# WebServer3_shield_wSD_FTDI.net
KiCad netlist of a schematic drawn in EAGLE
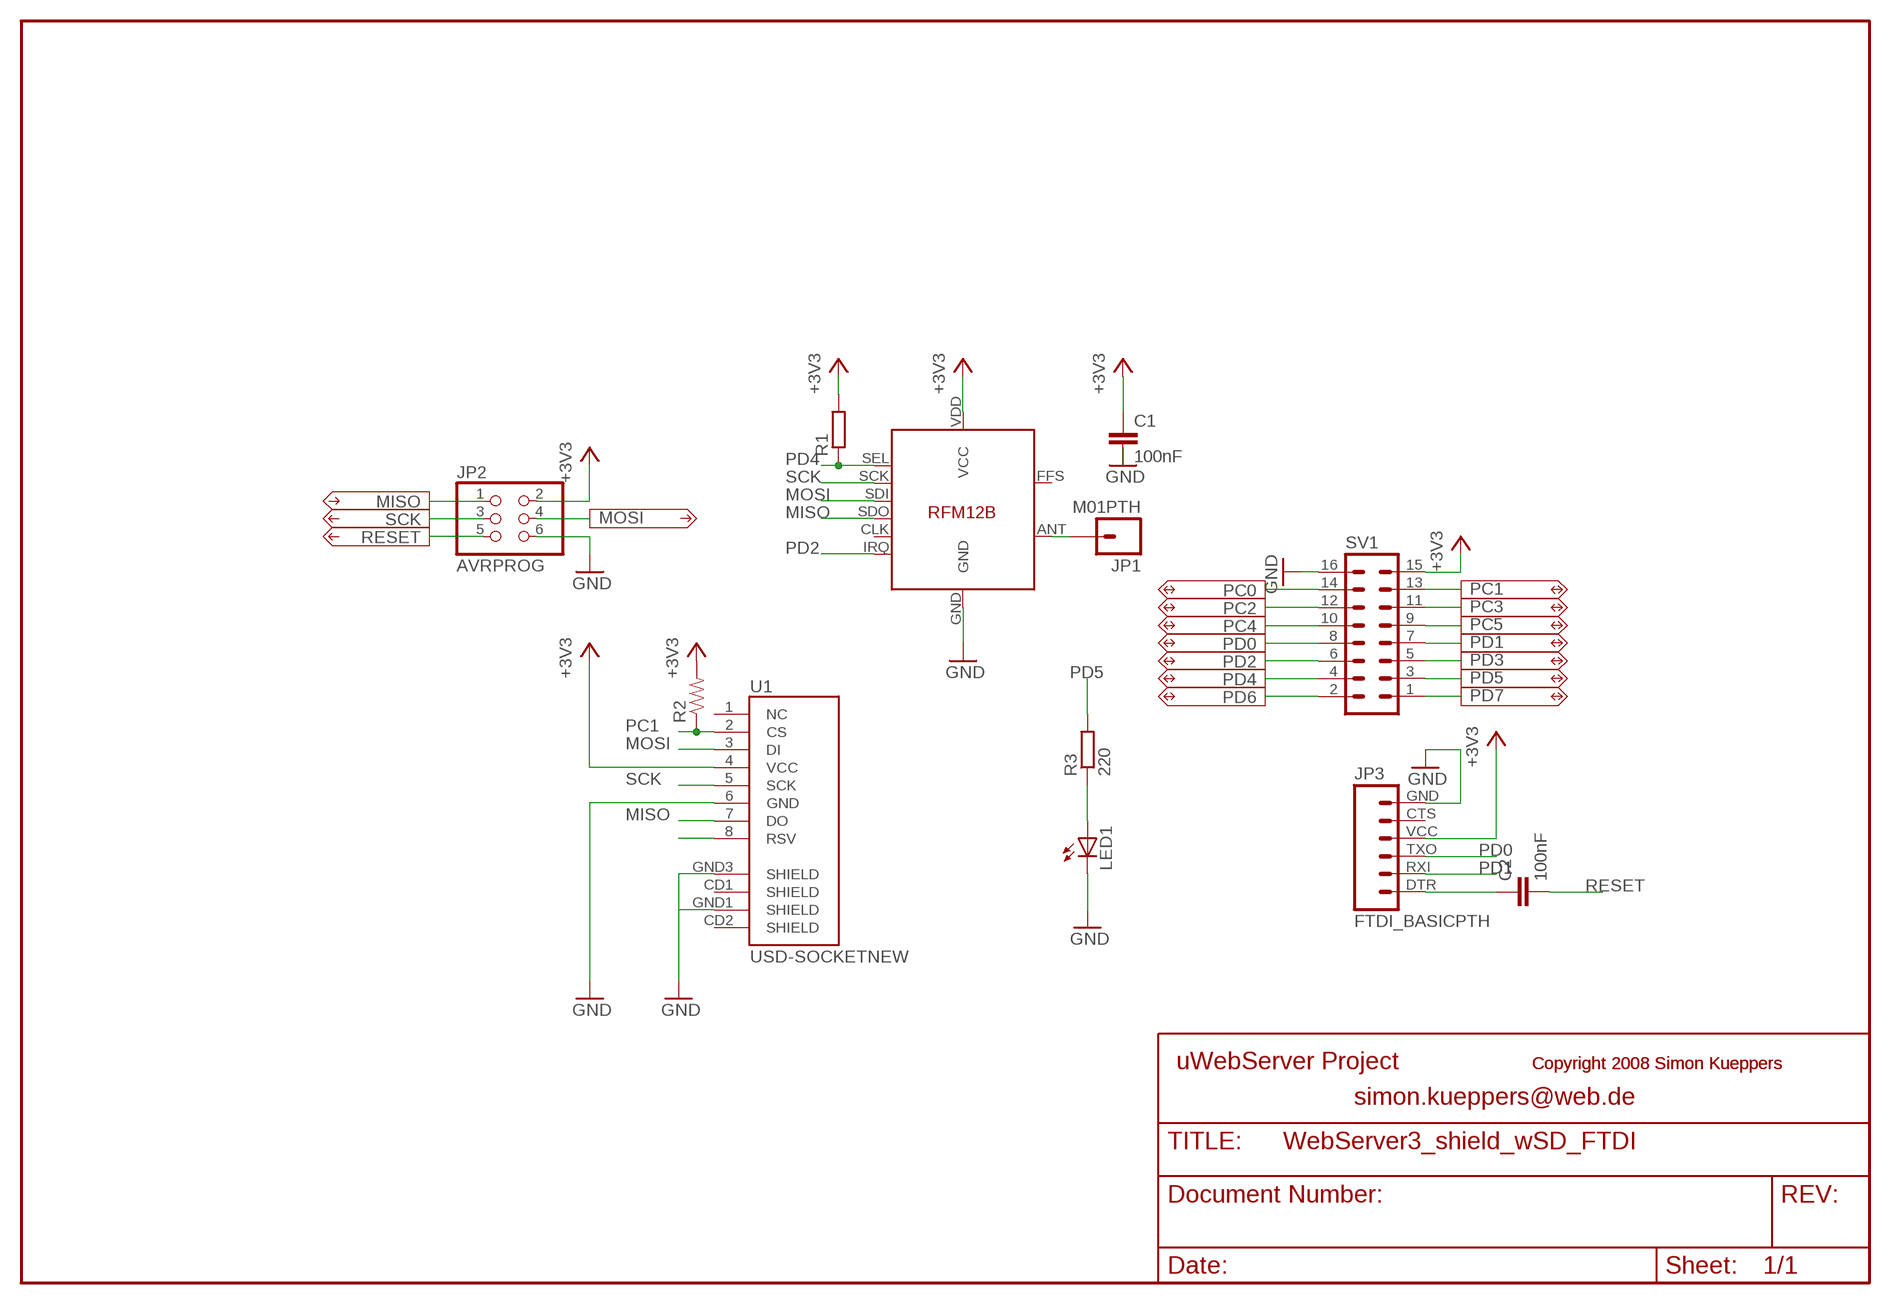
[diagram p0: schematic, sheet 1]

(export (version "E")
  (design (tool "Eeschema 10.0.6"))
  (components
    (comp (ref "C1")
      (value "100nF")
      (footprint "eagle-import:C0805")
      (libsource (lib "eagle-import") (part "C-EUC0805"))
    )
    (comp (ref "C2")
      (value "100nF")
      (footprint "eagle-import:C0805")
      (libsource (lib "eagle-import") (part "C-EUC0805"))
    )
    (comp (ref "JP1")
      (value "M01PTH")
      (footprint "eagle-import:1X01")
      (libsource (lib "eagle-import") (part "M01PTH"))
    )
    (comp (ref "JP2")
      (value "AVRPROG")
      (footprint "eagle-import:2X03")
      (libsource (lib "eagle-import") (part "PINHD-2X3_2.54"))
    )
    (comp (ref "JP3")
      (value "FTDI_BASICPTH")
      (footprint "eagle-import:FTDI_BASIC")
      (libsource (lib "eagle-import") (part "FTDI_BASICPTH"))
    )
    (comp (ref "LED1")
      (value "LED0603")
      (footprint "eagle-import:LED-0603")
      (libsource (lib "eagle-import") (part "LED0603"))
    )
    (comp (ref "R1")
      (value "R-EU_R0805")
      (footprint "eagle-import:R0805")
      (libsource (lib "eagle-import") (part "R-EU_R0805"))
    )
    (comp (ref "R2")
      (value "RESISTOR0805-RES")
      (footprint "eagle-import:0805")
      (libsource (lib "eagle-import") (part "RESISTOR0805-RES"))
    )
    (comp (ref "R3")
      (value "220")
      (footprint "eagle-import:R0805")
      (libsource (lib "eagle-import") (part "R-EU_R0805"))
    )
    (comp (ref "RFM12B")
      (value "RFM12B")
      (footprint "eagle-import:RFM12B")
      (libsource (lib "eagle-import") (part "RFM12B"))
    )
    (comp (ref "SV1")
      (value "MA08-2")
      (footprint "eagle-import:MA08-2")
      (libsource (lib "eagle-import") (part "MA08-2"))
    )
    (comp (ref "U1")
      (value "USD-SOCKETNEW")
      (footprint "eagle-import:MICRO-SD-SOCKET-PP")
      (libsource (lib "eagle-import") (part "USD-SOCKETNEW"))
    )
  )
  (nets
    (net (code "1") (name "+3V3") (class "Default")
      (node (ref "C1") (pin "1") (pinfunction "1_1") (pintype "passive"))
      (node (ref "JP2") (pin "2") (pinfunction "2_2") (pintype "passive"))
      (node (ref "JP3") (pin "VCC") (pinfunction "4_VCC") (pintype "passive"))
      (node (ref "R1") (pin "2") (pinfunction "2_2") (pintype "passive"))
      (node (ref "R2") (pin "2") (pinfunction "2_2") (pintype "passive"))
      (node (ref "RFM12B") (pin "VDD") (pinfunction "VCC_VDD") (pintype "power_in"))
      (node (ref "SV1") (pin "15") (pinfunction "15_15") (pintype "passive"))
      (node (ref "U1") (pin "4") (pinfunction "VCC_4") (pintype "bidirectional"))
    )
    (net (code "2") (name "/MISO") (class "Default")
      (node (ref "JP2") (pin "1") (pinfunction "1_1") (pintype "passive"))
      (node (ref "RFM12B") (pin "SDO") (pinfunction "SDO_SDO") (pintype "output"))
      (node (ref "U1") (pin "7") (pinfunction "DO_7") (pintype "bidirectional"))
    )
    (net (code "3") (name "/MOSI") (class "Default")
      (node (ref "JP2") (pin "4") (pinfunction "4_4") (pintype "passive"))
      (node (ref "RFM12B") (pin "SDI") (pinfunction "SDI_SDI") (pintype "input"))
      (node (ref "U1") (pin "3") (pinfunction "DI_3") (pintype "bidirectional"))
    )
    (net (code "4") (name "/PC1") (class "Default")
      (node (ref "R2") (pin "1") (pinfunction "1_1") (pintype "passive"))
      (node (ref "SV1") (pin "13") (pinfunction "13_13") (pintype "passive"))
      (node (ref "U1") (pin "2") (pinfunction "CS_2") (pintype "bidirectional"))
    )
    (net (code "5") (name "/PD0") (class "Default")
      (node (ref "JP3") (pin "TXO") (pinfunction "3_TXO") (pintype "passive"))
      (node (ref "SV1") (pin "8") (pinfunction "8_8") (pintype "passive"))
    )
    (net (code "6") (name "/PD1") (class "Default")
      (node (ref "JP3") (pin "RXI") (pinfunction "2_RXI") (pintype "passive"))
      (node (ref "SV1") (pin "7") (pinfunction "7_7") (pintype "passive"))
    )
    (net (code "7") (name "/PD2") (class "Default")
      (node (ref "RFM12B") (pin "IRQ") (pinfunction "IRQ_IRQ") (pintype "open_collector"))
      (node (ref "SV1") (pin "6") (pinfunction "6_6") (pintype "passive"))
    )
    (net (code "8") (name "/PD4") (class "Default")
      (node (ref "R1") (pin "1") (pinfunction "1_1") (pintype "passive"))
      (node (ref "RFM12B") (pin "SEL") (pinfunction "SEL_SEL") (pintype "input"))
      (node (ref "SV1") (pin "4") (pinfunction "4_4") (pintype "passive"))
    )
    (net (code "9") (name "/PD5") (class "Default")
      (node (ref "R3") (pin "2") (pinfunction "2_2") (pintype "passive"))
      (node (ref "SV1") (pin "3") (pinfunction "3_3") (pintype "passive"))
    )
    (net (code "10") (name "/RESET") (class "Default")
      (node (ref "C2") (pin "2") (pinfunction "2_2") (pintype "passive"))
      (node (ref "JP2") (pin "5") (pinfunction "5_5") (pintype "passive"))
    )
    (net (code "11") (name "/SCK") (class "Default")
      (node (ref "JP2") (pin "3") (pinfunction "3_3") (pintype "passive"))
      (node (ref "RFM12B") (pin "SCK") (pinfunction "SCK_SCK") (pintype "input"))
      (node (ref "U1") (pin "5") (pinfunction "SCK_5") (pintype "bidirectional"))
    )
    (net (code "12") (name "GND") (class "Default")
      (node (ref "C1") (pin "2") (pinfunction "2_2") (pintype "passive"))
      (node (ref "JP2") (pin "6") (pinfunction "6_6") (pintype "passive"))
      (node (ref "JP3") (pin "GND") (pinfunction "6_GND") (pintype "passive"))
      (node (ref "LED1") (pin "C") (pinfunction "C_C") (pintype "passive"))
      (node (ref "RFM12B") (pin "GND") (pinfunction "GND_GND") (pintype "power_in"))
      (node (ref "SV1") (pin "16") (pinfunction "16_16") (pintype "passive"))
      (node (ref "U1") (pin "6") (pinfunction "GND_6") (pintype "bidirectional"))
      (node (ref "U1") (pin "GND3") (pinfunction "SHIELD_GND3") (pintype "bidirectional"))
    )
    (net (code "13") (name "Net-(JP1-Pad1)") (class "Default")
      (node (ref "JP1") (pin "1") (pinfunction "1_1") (pintype "passive"))
      (node (ref "RFM12B") (pin "ANT") (pinfunction "ANT_ANT") (pintype "passive"))
    )
    (net (code "14") (name "Net-(JP3-1)") (class "Default")
      (node (ref "C2") (pin "1") (pinfunction "1_1") (pintype "passive"))
      (node (ref "JP3") (pin "DTR") (pinfunction "1_DTR") (pintype "passive"))
    )
    (net (code "15") (name "Net-(LED1-PadA)") (class "Default")
      (node (ref "LED1") (pin "A") (pinfunction "A_A") (pintype "passive"))
      (node (ref "R3") (pin "1") (pinfunction "1_1") (pintype "passive"))
    )
    (net (code "16") (name "unconnected-(JP3-5-PadCTS)") (class "Default")
      (node (ref "JP3") (pin "CTS") (pinfunction "5_CTS") (pintype "passive"))
    )
    (net (code "17") (name "unconnected-(RFM12B-PadCLK)") (class "Default")
      (node (ref "RFM12B") (pin "CLK") (pinfunction "CLK_CLK") (pintype "output"))
    )
    (net (code "18") (name "unconnected-(RFM12B-PadFFS)") (class "Default")
      (node (ref "RFM12B") (pin "FFS") (pinfunction "FFS_FFS") (pintype "bidirectional"))
    )
    (net (code "19") (name "unconnected-(SV1-Pad1)") (class "Default")
      (node (ref "SV1") (pin "1") (pinfunction "1_1") (pintype "passive"))
    )
    (net (code "20") (name "unconnected-(SV1-Pad2)") (class "Default")
      (node (ref "SV1") (pin "2") (pinfunction "2_2") (pintype "passive"))
    )
    (net (code "21") (name "unconnected-(SV1-Pad5)") (class "Default")
      (node (ref "SV1") (pin "5") (pinfunction "5_5") (pintype "passive"))
    )
    (net (code "22") (name "unconnected-(SV1-Pad9)") (class "Default")
      (node (ref "SV1") (pin "9") (pinfunction "9_9") (pintype "passive"))
    )
    (net (code "23") (name "unconnected-(SV1-Pad10)") (class "Default")
      (node (ref "SV1") (pin "10") (pinfunction "10_10") (pintype "passive"))
    )
    (net (code "24") (name "unconnected-(SV1-Pad11)") (class "Default")
      (node (ref "SV1") (pin "11") (pinfunction "11_11") (pintype "passive"))
    )
    (net (code "25") (name "unconnected-(SV1-Pad12)") (class "Default")
      (node (ref "SV1") (pin "12") (pinfunction "12_12") (pintype "passive"))
    )
    (net (code "26") (name "unconnected-(SV1-Pad14)") (class "Default")
      (node (ref "SV1") (pin "14") (pinfunction "14_14") (pintype "passive"))
    )
    (net (code "27") (name "unconnected-(U1-NC-Pad1)") (class "Default")
      (node (ref "U1") (pin "1") (pinfunction "NC_1") (pintype "bidirectional"))
    )
    (net (code "28") (name "unconnected-(U1-RSV-Pad8)") (class "Default")
      (node (ref "U1") (pin "8") (pinfunction "RSV_8") (pintype "bidirectional"))
    )
    (net (code "29") (name "unconnected-(U1-SHIELD-PadCD1)") (class "Default")
      (node (ref "U1") (pin "CD1") (pinfunction "SHIELD_CD1") (pintype "bidirectional"))
    )
    (net (code "30") (name "unconnected-(U1-SHIELD-PadCD2)") (class "Default")
      (node (ref "U1") (pin "CD2") (pinfunction "SHIELD_CD2") (pintype "bidirectional"))
    )
    (net (code "31") (name "unconnected-(U1-SHIELD-PadGND1)") (class "Default")
      (node (ref "U1") (pin "GND1") (pinfunction "SHIELD_GND1") (pintype "bidirectional"))
    )
  )
)
